# B.net
KiCad netlist of a schematic drawn in Altium Designer
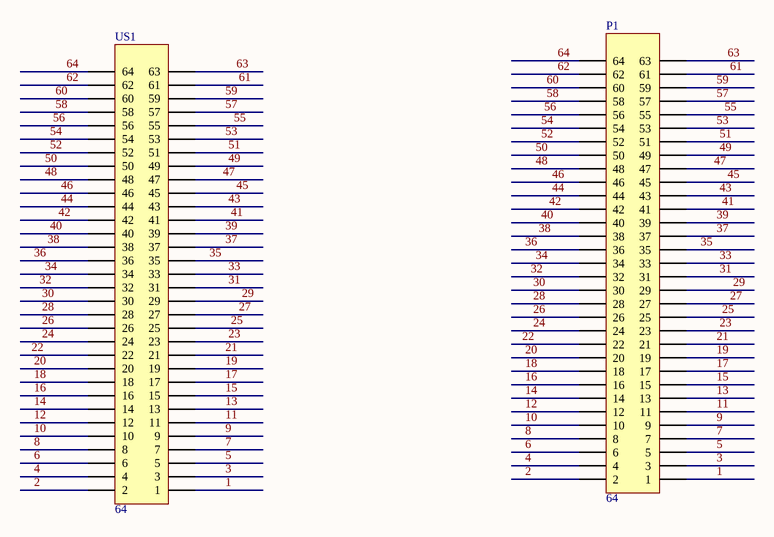
[diagram p0: B.SchDoc]

(export (version "E")
  (design (tool "Eeschema 10.0.6"))
  (components
    (comp (ref "P1") (value "64") (footprint "64-1") (libsource (lib "1299") (part "64")))
    (comp (ref "US1") (value "64") (footprint "TQFP64") (libsource (lib "1299") (part "64")))
  )
  (nets
    (net (code "1") (name "/1") (class "Default")
      (node (ref "P1") (pin "1") (pinfunction "1_1") (pintype "passive"))
      (node (ref "US1") (pin "1") (pinfunction "1_1") (pintype "passive"))
    )
    (net (code "2") (name "/2") (class "Default")
      (node (ref "P1") (pin "2") (pinfunction "2_2") (pintype "passive"))
      (node (ref "US1") (pin "2") (pinfunction "2_2") (pintype "passive"))
    )
    (net (code "3") (name "/3") (class "Default")
      (node (ref "P1") (pin "3") (pinfunction "3_3") (pintype "passive"))
      (node (ref "US1") (pin "3") (pinfunction "3_3") (pintype "passive"))
    )
    (net (code "4") (name "/4") (class "Default")
      (node (ref "P1") (pin "4") (pinfunction "4_4") (pintype "passive"))
      (node (ref "US1") (pin "4") (pinfunction "4_4") (pintype "passive"))
    )
    (net (code "5") (name "/5") (class "Default")
      (node (ref "P1") (pin "5") (pinfunction "5_5") (pintype "passive"))
      (node (ref "US1") (pin "5") (pinfunction "5_5") (pintype "passive"))
    )
    (net (code "6") (name "/6") (class "Default")
      (node (ref "P1") (pin "6") (pinfunction "6_6") (pintype "passive"))
      (node (ref "US1") (pin "6") (pinfunction "6_6") (pintype "passive"))
    )
    (net (code "7") (name "/7") (class "Default")
      (node (ref "P1") (pin "7") (pinfunction "7_7") (pintype "passive"))
      (node (ref "US1") (pin "7") (pinfunction "7_7") (pintype "passive"))
    )
    (net (code "8") (name "/8") (class "Default")
      (node (ref "P1") (pin "8") (pinfunction "8_8") (pintype "passive"))
      (node (ref "US1") (pin "8") (pinfunction "8_8") (pintype "passive"))
    )
    (net (code "9") (name "/9") (class "Default")
      (node (ref "P1") (pin "9") (pinfunction "9_9") (pintype "passive"))
      (node (ref "US1") (pin "9") (pinfunction "9_9") (pintype "passive"))
    )
    (net (code "10") (name "/10") (class "Default")
      (node (ref "P1") (pin "10") (pinfunction "10_10") (pintype "passive"))
      (node (ref "US1") (pin "10") (pinfunction "10_10") (pintype "passive"))
    )
    (net (code "11") (name "/11") (class "Default")
      (node (ref "P1") (pin "11") (pinfunction "11_11") (pintype "passive"))
      (node (ref "US1") (pin "11") (pinfunction "11_11") (pintype "passive"))
    )
    (net (code "12") (name "/12") (class "Default")
      (node (ref "P1") (pin "12") (pinfunction "12_12") (pintype "passive"))
      (node (ref "US1") (pin "12") (pinfunction "12_12") (pintype "passive"))
    )
    (net (code "13") (name "/13") (class "Default")
      (node (ref "P1") (pin "13") (pinfunction "13_13") (pintype "passive"))
      (node (ref "US1") (pin "13") (pinfunction "13_13") (pintype "passive"))
    )
    (net (code "14") (name "/14") (class "Default")
      (node (ref "P1") (pin "14") (pinfunction "14_14") (pintype "passive"))
      (node (ref "US1") (pin "14") (pinfunction "14_14") (pintype "passive"))
    )
    (net (code "15") (name "/15") (class "Default")
      (node (ref "P1") (pin "15") (pinfunction "15_15") (pintype "passive"))
      (node (ref "US1") (pin "15") (pinfunction "15_15") (pintype "passive"))
    )
    (net (code "16") (name "/16") (class "Default")
      (node (ref "P1") (pin "16") (pinfunction "16_16") (pintype "passive"))
      (node (ref "US1") (pin "16") (pinfunction "16_16") (pintype "passive"))
    )
    (net (code "17") (name "/17") (class "Default")
      (node (ref "P1") (pin "17") (pinfunction "17_17") (pintype "passive"))
      (node (ref "US1") (pin "17") (pinfunction "17_17") (pintype "passive"))
    )
    (net (code "18") (name "/18") (class "Default")
      (node (ref "P1") (pin "18") (pinfunction "18_18") (pintype "passive"))
      (node (ref "US1") (pin "18") (pinfunction "18_18") (pintype "passive"))
    )
    (net (code "19") (name "/19") (class "Default")
      (node (ref "P1") (pin "19") (pinfunction "19_19") (pintype "passive"))
      (node (ref "US1") (pin "19") (pinfunction "19_19") (pintype "passive"))
    )
    (net (code "20") (name "/20") (class "Default")
      (node (ref "P1") (pin "20") (pinfunction "20_20") (pintype "passive"))
      (node (ref "US1") (pin "20") (pinfunction "20_20") (pintype "passive"))
    )
    (net (code "21") (name "/21") (class "Default")
      (node (ref "P1") (pin "21") (pinfunction "21_21") (pintype "passive"))
      (node (ref "US1") (pin "21") (pinfunction "21_21") (pintype "passive"))
    )
    (net (code "22") (name "/22") (class "Default")
      (node (ref "P1") (pin "22") (pinfunction "22_22") (pintype "passive"))
      (node (ref "US1") (pin "22") (pinfunction "22_22") (pintype "passive"))
    )
    (net (code "23") (name "/23") (class "Default")
      (node (ref "P1") (pin "23") (pinfunction "23_23") (pintype "passive"))
      (node (ref "US1") (pin "23") (pinfunction "23_23") (pintype "passive"))
    )
    (net (code "24") (name "/24") (class "Default")
      (node (ref "P1") (pin "24") (pinfunction "24_24") (pintype "passive"))
      (node (ref "US1") (pin "24") (pinfunction "24_24") (pintype "passive"))
    )
    (net (code "25") (name "/25") (class "Default")
      (node (ref "P1") (pin "25") (pinfunction "25_25") (pintype "passive"))
      (node (ref "US1") (pin "25") (pinfunction "25_25") (pintype "passive"))
    )
    (net (code "26") (name "/26") (class "Default")
      (node (ref "P1") (pin "26") (pinfunction "26_26") (pintype "passive"))
      (node (ref "US1") (pin "26") (pinfunction "26_26") (pintype "passive"))
    )
    (net (code "27") (name "/27") (class "Default")
      (node (ref "P1") (pin "27") (pinfunction "27_27") (pintype "passive"))
      (node (ref "US1") (pin "27") (pinfunction "27_27") (pintype "passive"))
    )
    (net (code "28") (name "/28") (class "Default")
      (node (ref "P1") (pin "28") (pinfunction "28_28") (pintype "passive"))
      (node (ref "US1") (pin "28") (pinfunction "28_28") (pintype "passive"))
    )
    (net (code "29") (name "/29") (class "Default")
      (node (ref "P1") (pin "29") (pinfunction "29_29") (pintype "passive"))
      (node (ref "US1") (pin "29") (pinfunction "29_29") (pintype "passive"))
    )
    (net (code "30") (name "/30") (class "Default")
      (node (ref "P1") (pin "30") (pinfunction "30_30") (pintype "passive"))
      (node (ref "US1") (pin "30") (pinfunction "30_30") (pintype "passive"))
    )
    (net (code "31") (name "/31") (class "Default")
      (node (ref "P1") (pin "31") (pinfunction "31_31") (pintype "passive"))
      (node (ref "US1") (pin "31") (pinfunction "31_31") (pintype "passive"))
    )
    (net (code "32") (name "/32") (class "Default")
      (node (ref "P1") (pin "32") (pinfunction "32_32") (pintype "passive"))
      (node (ref "US1") (pin "32") (pinfunction "32_32") (pintype "passive"))
    )
    (net (code "33") (name "/33") (class "Default")
      (node (ref "P1") (pin "33") (pinfunction "33_33") (pintype "passive"))
      (node (ref "US1") (pin "33") (pinfunction "33_33") (pintype "passive"))
    )
    (net (code "34") (name "/34") (class "Default")
      (node (ref "P1") (pin "34") (pinfunction "34_34") (pintype "passive"))
      (node (ref "US1") (pin "34") (pinfunction "34_34") (pintype "passive"))
    )
    (net (code "35") (name "/35") (class "Default")
      (node (ref "P1") (pin "35") (pinfunction "35_35") (pintype "passive"))
      (node (ref "US1") (pin "35") (pinfunction "35_35") (pintype "passive"))
    )
    (net (code "36") (name "/36") (class "Default")
      (node (ref "P1") (pin "36") (pinfunction "36_36") (pintype "passive"))
      (node (ref "US1") (pin "36") (pinfunction "36_36") (pintype "passive"))
    )
    (net (code "37") (name "/37") (class "Default")
      (node (ref "P1") (pin "37") (pinfunction "37_37") (pintype "passive"))
      (node (ref "US1") (pin "37") (pinfunction "37_37") (pintype "passive"))
    )
    (net (code "38") (name "/38") (class "Default")
      (node (ref "P1") (pin "38") (pinfunction "38_38") (pintype "passive"))
      (node (ref "US1") (pin "38") (pinfunction "38_38") (pintype "passive"))
    )
    (net (code "39") (name "/39") (class "Default")
      (node (ref "P1") (pin "39") (pinfunction "39_39") (pintype "passive"))
      (node (ref "US1") (pin "39") (pinfunction "39_39") (pintype "passive"))
    )
    (net (code "40") (name "/40") (class "Default")
      (node (ref "P1") (pin "40") (pinfunction "40_40") (pintype "passive"))
      (node (ref "US1") (pin "40") (pinfunction "40_40") (pintype "passive"))
    )
    (net (code "41") (name "/41") (class "Default")
      (node (ref "P1") (pin "41") (pinfunction "41_41") (pintype "passive"))
      (node (ref "US1") (pin "41") (pinfunction "41_41") (pintype "passive"))
    )
    (net (code "42") (name "/42") (class "Default")
      (node (ref "P1") (pin "42") (pinfunction "42_42") (pintype "passive"))
      (node (ref "US1") (pin "42") (pinfunction "42_42") (pintype "passive"))
    )
    (net (code "43") (name "/43") (class "Default")
      (node (ref "P1") (pin "43") (pinfunction "43_43") (pintype "passive"))
      (node (ref "US1") (pin "43") (pinfunction "43_43") (pintype "passive"))
    )
    (net (code "44") (name "/44") (class "Default")
      (node (ref "P1") (pin "44") (pinfunction "44_44") (pintype "passive"))
      (node (ref "US1") (pin "44") (pinfunction "44_44") (pintype "passive"))
    )
    (net (code "45") (name "/45") (class "Default")
      (node (ref "P1") (pin "45") (pinfunction "45_45") (pintype "passive"))
      (node (ref "US1") (pin "45") (pinfunction "45_45") (pintype "passive"))
    )
    (net (code "46") (name "/46") (class "Default")
      (node (ref "P1") (pin "46") (pinfunction "46_46") (pintype "passive"))
      (node (ref "US1") (pin "46") (pinfunction "46_46") (pintype "passive"))
    )
    (net (code "47") (name "/47") (class "Default")
      (node (ref "P1") (pin "47") (pinfunction "47_47") (pintype "passive"))
      (node (ref "US1") (pin "47") (pinfunction "47_47") (pintype "passive"))
    )
    (net (code "48") (name "/48") (class "Default")
      (node (ref "P1") (pin "48") (pinfunction "48_48") (pintype "passive"))
      (node (ref "US1") (pin "48") (pinfunction "48_48") (pintype "passive"))
    )
    (net (code "49") (name "/49") (class "Default")
      (node (ref "P1") (pin "49") (pinfunction "49_49") (pintype "passive"))
      (node (ref "US1") (pin "49") (pinfunction "49_49") (pintype "passive"))
    )
    (net (code "50") (name "/50") (class "Default")
      (node (ref "P1") (pin "50") (pinfunction "50_50") (pintype "passive"))
      (node (ref "US1") (pin "50") (pinfunction "50_50") (pintype "passive"))
    )
    (net (code "51") (name "/51") (class "Default")
      (node (ref "P1") (pin "51") (pinfunction "51_51") (pintype "passive"))
      (node (ref "US1") (pin "51") (pinfunction "51_51") (pintype "passive"))
    )
    (net (code "52") (name "/52") (class "Default")
      (node (ref "P1") (pin "52") (pinfunction "52_52") (pintype "passive"))
      (node (ref "US1") (pin "52") (pinfunction "52_52") (pintype "passive"))
    )
    (net (code "53") (name "/53") (class "Default")
      (node (ref "P1") (pin "53") (pinfunction "53_53") (pintype "passive"))
      (node (ref "US1") (pin "53") (pinfunction "53_53") (pintype "passive"))
    )
    (net (code "54") (name "/54") (class "Default")
      (node (ref "P1") (pin "54") (pinfunction "54_54") (pintype "passive"))
      (node (ref "US1") (pin "54") (pinfunction "54_54") (pintype "passive"))
    )
    (net (code "55") (name "/55") (class "Default")
      (node (ref "P1") (pin "55") (pinfunction "55_55") (pintype "passive"))
      (node (ref "US1") (pin "55") (pinfunction "55_55") (pintype "passive"))
    )
    (net (code "56") (name "/56") (class "Default")
      (node (ref "P1") (pin "56") (pinfunction "56_56") (pintype "passive"))
      (node (ref "US1") (pin "56") (pinfunction "56_56") (pintype "passive"))
    )
    (net (code "57") (name "/57") (class "Default")
      (node (ref "P1") (pin "57") (pinfunction "57_57") (pintype "passive"))
      (node (ref "US1") (pin "57") (pinfunction "57_57") (pintype "passive"))
    )
    (net (code "58") (name "/58") (class "Default")
      (node (ref "P1") (pin "58") (pinfunction "58_58") (pintype "passive"))
      (node (ref "US1") (pin "58") (pinfunction "58_58") (pintype "passive"))
    )
    (net (code "59") (name "/59") (class "Default")
      (node (ref "P1") (pin "59") (pinfunction "59_59") (pintype "passive"))
      (node (ref "US1") (pin "59") (pinfunction "59_59") (pintype "passive"))
    )
    (net (code "60") (name "/60") (class "Default")
      (node (ref "P1") (pin "60") (pinfunction "60_60") (pintype "passive"))
      (node (ref "US1") (pin "60") (pinfunction "60_60") (pintype "passive"))
    )
    (net (code "61") (name "/61") (class "Default")
      (node (ref "P1") (pin "61") (pinfunction "61_61") (pintype "passive"))
      (node (ref "US1") (pin "61") (pinfunction "61_61") (pintype "passive"))
    )
    (net (code "62") (name "/62") (class "Default")
      (node (ref "P1") (pin "62") (pinfunction "62_62") (pintype "passive"))
      (node (ref "US1") (pin "62") (pinfunction "62_62") (pintype "passive"))
    )
    (net (code "63") (name "/63") (class "Default")
      (node (ref "P1") (pin "63") (pinfunction "63_63") (pintype "passive"))
      (node (ref "US1") (pin "63") (pinfunction "63_63") (pintype "passive"))
    )
    (net (code "64") (name "/64") (class "Default")
      (node (ref "P1") (pin "64") (pinfunction "64_64") (pintype "passive"))
      (node (ref "US1") (pin "64") (pinfunction "64_64") (pintype "passive"))
    )
  )
)
